# Display.net
KiCad netlist of a schematic drawn in Altium Designer
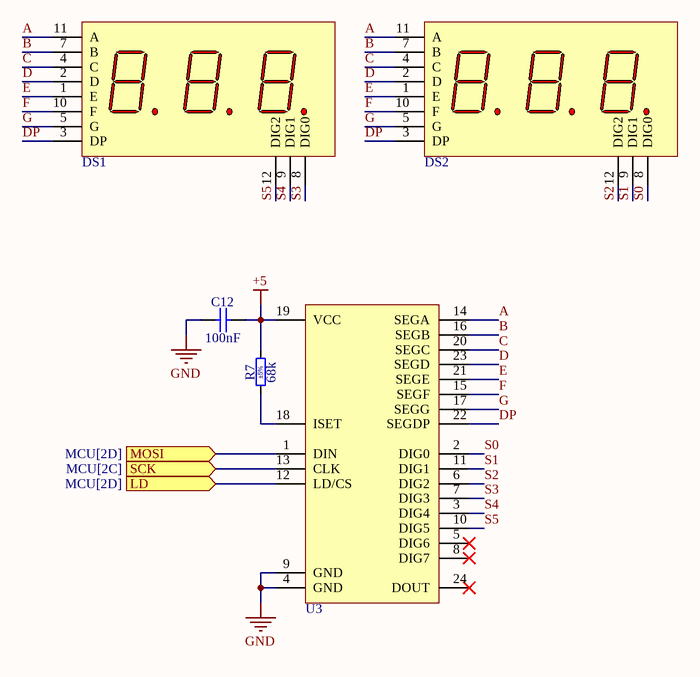
[diagram p0: Display.SchDoc]

(export (version "E")
  (design (tool "Eeschema 10.0.6"))
  (components
    (comp (ref "C12")
      (value "100nF")
      (footprint "CAPC2012X135N")
      (description "Non-polarised capacitor")
      (fields
        (field (name "PART NUMBER") "CC0805_100NF_50V_10%_X7R")
        (field (name "VOLTAGE") "50V")
        (field (name "AUTHOR") "CERN DEM JLC")
      )
      (libsource (lib "Capacitors") (part "Capacitor - non polarized"))
    )
    (comp (ref "DS1")
      (value "7SEGMENT-3DIG-CC")
      (footprint "7SEGMENT-3DIG")
      (libsource (lib "IKU-LIB") (part "7SEGMENT-3DIG-CC"))
    )
    (comp (ref "DS2")
      (value "7SEGMENT-3DIG-CC")
      (footprint "7SEGMENT-3DIG")
      (libsource (lib "IKU-LIB") (part "7SEGMENT-3DIG-CC"))
    )
    (comp (ref "R7")
      (value "68k")
      (footprint "RESC2012X60N")
      (description "Resistor - 5%")
      (fields
        (field (name "TOLERANCE") "±5%")
        (field (name "PART NUMBER") "R0805_68K_1%_0.125W_100PPM")
        (field (name "POWER") "0.125W")
        (field (name "AUTHOR") "CERN DEM JLC")
      )
      (libsource (lib "Resistors") (part "Resistor - 1%"))
    )
    (comp (ref "U3")
      (value "MAX7219CWG+")
      (footprint "SOIC-24W")
      (description "LED Driver, 7-Segment, MOS, PDSO24")
      (fields (field (name "MANUFACTURER") "Maxim"))
      (libsource (lib "IKU-LIB") (part "MAX7219CWG+"))
    )
  )
  (nets
    (net (code "1") (name "+5") (class "Default")
      (node (ref "C12") (pin "2") (pinfunction "2_2") (pintype "passive"))
      (node (ref "R7") (pin "2") (pinfunction "2_2") (pintype "passive"))
      (node (ref "U3") (pin "19") (pinfunction "VCC_19") (pintype "passive"))
    )
    (net (code "2") (name "/A") (class "Default")
      (node (ref "DS1") (pin "11") (pinfunction "A_11") (pintype "passive"))
      (node (ref "DS2") (pin "11") (pinfunction "A_11") (pintype "passive"))
      (node (ref "U3") (pin "14") (pinfunction "SEGA_14") (pintype "passive"))
    )
    (net (code "3") (name "/B") (class "Default")
      (node (ref "DS1") (pin "7") (pinfunction "B_7") (pintype "passive"))
      (node (ref "DS2") (pin "7") (pinfunction "B_7") (pintype "passive"))
      (node (ref "U3") (pin "16") (pinfunction "SEGB_16") (pintype "passive"))
    )
    (net (code "4") (name "/C") (class "Default")
      (node (ref "DS1") (pin "4") (pinfunction "C_4") (pintype "passive"))
      (node (ref "DS2") (pin "4") (pinfunction "C_4") (pintype "passive"))
      (node (ref "U3") (pin "20") (pinfunction "SEGC_20") (pintype "passive"))
    )
    (net (code "5") (name "/D") (class "Default")
      (node (ref "DS1") (pin "2") (pinfunction "D_2") (pintype "passive"))
      (node (ref "DS2") (pin "2") (pinfunction "D_2") (pintype "passive"))
      (node (ref "U3") (pin "23") (pinfunction "SEGD_23") (pintype "passive"))
    )
    (net (code "6") (name "/DP") (class "Default")
      (node (ref "DS1") (pin "3") (pinfunction "DP_3") (pintype "passive"))
      (node (ref "DS2") (pin "3") (pinfunction "DP_3") (pintype "passive"))
      (node (ref "U3") (pin "22") (pinfunction "SEGDP_22") (pintype "passive"))
    )
    (net (code "7") (name "/E") (class "Default")
      (node (ref "DS1") (pin "1") (pinfunction "E_1") (pintype "passive"))
      (node (ref "DS2") (pin "1") (pinfunction "E_1") (pintype "passive"))
      (node (ref "U3") (pin "21") (pinfunction "SEGE_21") (pintype "passive"))
    )
    (net (code "8") (name "/F") (class "Default")
      (node (ref "DS1") (pin "10") (pinfunction "F_10") (pintype "passive"))
      (node (ref "DS2") (pin "10") (pinfunction "F_10") (pintype "passive"))
      (node (ref "U3") (pin "15") (pinfunction "SEGF_15") (pintype "passive"))
    )
    (net (code "9") (name "/G") (class "Default")
      (node (ref "DS1") (pin "5") (pinfunction "G_5") (pintype "passive"))
      (node (ref "DS2") (pin "5") (pinfunction "G_5") (pintype "passive"))
      (node (ref "U3") (pin "17") (pinfunction "SEGG_17") (pintype "passive"))
    )
    (net (code "10") (name "/LD") (class "Default")
      (node (ref "U3") (pin "12") (pinfunction "LD/CS_12") (pintype "passive"))
    )
    (net (code "11") (name "/MOSI") (class "Default")
      (node (ref "U3") (pin "1") (pinfunction "DIN_1") (pintype "passive"))
    )
    (net (code "12") (name "/S0") (class "Default")
      (node (ref "DS2") (pin "8") (pinfunction "DIG0_8") (pintype "passive"))
      (node (ref "U3") (pin "2") (pinfunction "DIG0_2") (pintype "passive"))
    )
    (net (code "13") (name "/S1") (class "Default")
      (node (ref "DS2") (pin "9") (pinfunction "DIG1_9") (pintype "passive"))
      (node (ref "U3") (pin "11") (pinfunction "DIG1_11") (pintype "passive"))
    )
    (net (code "14") (name "/S2") (class "Default")
      (node (ref "DS2") (pin "12") (pinfunction "DIG2_12") (pintype "passive"))
      (node (ref "U3") (pin "6") (pinfunction "DIG2_6") (pintype "passive"))
    )
    (net (code "15") (name "/S3") (class "Default")
      (node (ref "DS1") (pin "8") (pinfunction "DIG0_8") (pintype "passive"))
      (node (ref "U3") (pin "7") (pinfunction "DIG3_7") (pintype "passive"))
    )
    (net (code "16") (name "/S4") (class "Default")
      (node (ref "DS1") (pin "9") (pinfunction "DIG1_9") (pintype "passive"))
      (node (ref "U3") (pin "3") (pinfunction "DIG4_3") (pintype "passive"))
    )
    (net (code "17") (name "/S5") (class "Default")
      (node (ref "DS1") (pin "12") (pinfunction "DIG2_12") (pintype "passive"))
      (node (ref "U3") (pin "10") (pinfunction "DIG5_10") (pintype "passive"))
    )
    (net (code "18") (name "/SCK") (class "Default")
      (node (ref "U3") (pin "13") (pinfunction "CLK_13") (pintype "passive"))
    )
    (net (code "19") (name "GND") (class "Default")
      (node (ref "C12") (pin "1") (pinfunction "1_1") (pintype "passive"))
      (node (ref "U3") (pin "4") (pinfunction "GND_4") (pintype "passive"))
      (node (ref "U3") (pin "9") (pinfunction "GND_9") (pintype "passive"))
    )
    (net (code "20") (name "Net-(U3-ISET)") (class "Default")
      (node (ref "R7") (pin "1") (pinfunction "1_1") (pintype "passive"))
      (node (ref "U3") (pin "18") (pinfunction "ISET_18") (pintype "passive"))
    )
    (net (code "21") (name "unconnected-(U3-DIG6-Pad5)") (class "Default")
      (node (ref "U3") (pin "5") (pinfunction "DIG6_5") (pintype "passive+no_connect"))
    )
    (net (code "22") (name "unconnected-(U3-DIG7-Pad8)") (class "Default")
      (node (ref "U3") (pin "8") (pinfunction "DIG7_8") (pintype "passive+no_connect"))
    )
    (net (code "23") (name "unconnected-(U3-DOUT-Pad24)") (class "Default")
      (node (ref "U3") (pin "24") (pinfunction "DOUT_24") (pintype "passive+no_connect"))
    )
  )
)
